# DS145-1_0-B.net
KiCad netlist of a schematic drawn in Altium Designer
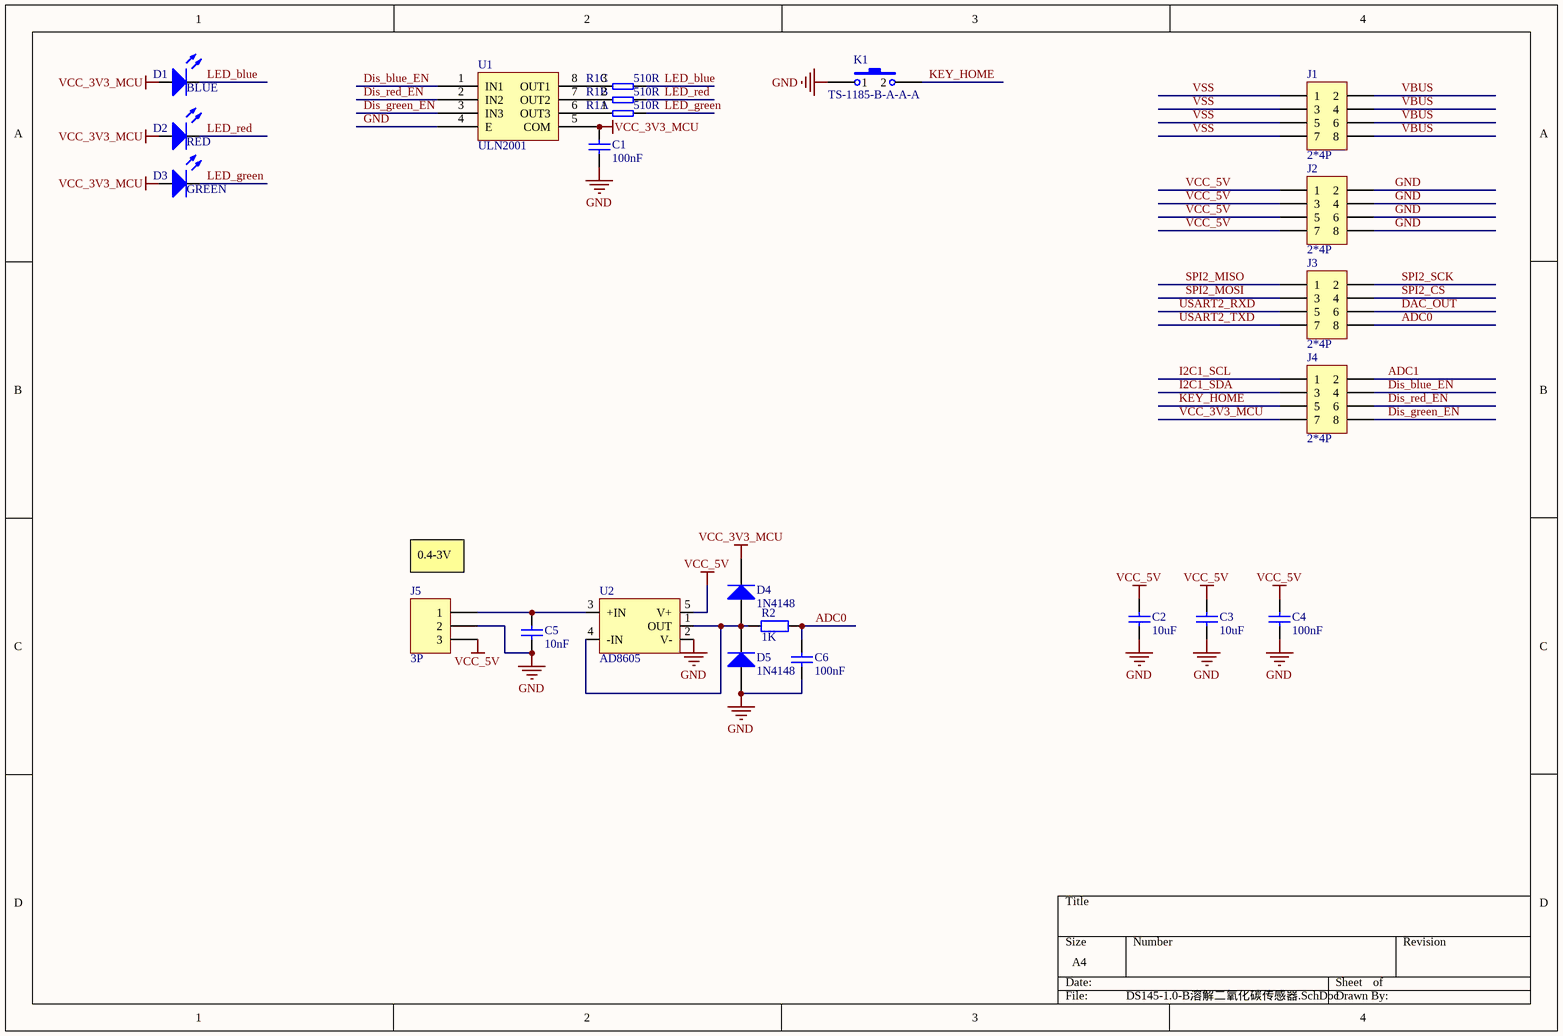
[diagram p0: DS145-1.0-B溶解二氧化碳传感器.SchDoc]

(export (version "E")
  (design (tool "Eeschema 10.0.6"))
  (components
    (comp (ref "C1")
      (value "100nF")
      (footprint "0603CAP")
      (description "贴片电容")
      (fields (field (name "Comment") "SMDCAP00013"))
      (libsource (lib "AD_SCH") (part "MLCC 100nF 50V ±10％ 0603"))
    )
    (comp (ref "C2")
      (value "10uF")
      (footprint "0603CAP")
      (description "贴片电容")
      (fields (field (name "Comment") "SMDCAP00016"))
      (libsource (lib "AD_SCH") (part "MLCC 10uF 50V ±10％ 0603"))
    )
    (comp (ref "C3")
      (value "10uF")
      (footprint "0603CAP")
      (description "贴片电容")
      (fields (field (name "Comment") "SMDCAP00016"))
      (libsource (lib "AD_SCH") (part "MLCC 10uF 50V ±10％ 0603"))
    )
    (comp (ref "C4")
      (value "100nF")
      (footprint "0603CAP")
      (description "贴片电容")
      (fields (field (name "Comment") "SMDCAP00013"))
      (libsource (lib "AD_SCH") (part "MLCC 100nF 50V ±10％ 0603"))
    )
    (comp (ref "C5")
      (value "10nF")
      (footprint "0603CAP")
      (description "贴片电容")
      (fields (field (name "Comment") "SMDCAP00013"))
      (libsource (lib "AD_SCH") (part "MLCC 100nF 50V ±10％ 0603"))
    )
    (comp (ref "C6")
      (value "100nF")
      (footprint "0603CAP")
      (description "贴片电容")
      (fields (field (name "Comment") "SMDCAP00013"))
      (libsource (lib "AD_SCH") (part "MLCC 100nF 50V ±10％ 0603"))
    )
    (comp (ref "D1")
      (value "BLUE")
      (footprint "LED_0805")
      (description "贴片LED")
      (fields (field (name "Comment") "SMDLED00010"))
      (libsource (lib "AD_SCH") (part "Chip 蓝色LED 0805"))
    )
    (comp (ref "D2")
      (value "RED")
      (footprint "LED_0805")
      (description "贴片LED")
      (fields (field (name "Comment") "SMDLED00003"))
      (libsource (lib "AD_SCH") (part "Chip 红色LED 0805"))
    )
    (comp (ref "D3")
      (value "GREEN")
      (footprint "LED_0805")
      (description "贴片LED")
      (fields (field (name "Comment") "Chip 翠绿LED 0805"))
      (libsource (lib "AD_SCH") (part "Chip 翠绿LED 0805"))
    )
    (comp (ref "D4")
      (value "1N4148")
      (footprint "SOD-123")
      (description "贴片开关二极管 T4")
      (fields (field (name "Comment") "DIPDIODE02001"))
      (libsource (lib "AD_SCH") (part "1N4148W"))
    )
    (comp (ref "D5")
      (value "1N4148")
      (footprint "SOD-123")
      (description "贴片开关二极管 T4")
      (fields (field (name "Comment") "DIPDIODE02001"))
      (libsource (lib "AD_SCH") (part "1N4148W"))
    )
    (comp (ref "J1")
      (value "2*4P")
      (footprint "X1321WVS-2x04J-C40D53")
      (description "双排针2x4P 立贴 1.27mm")
      (fields (field (name "Comment") "X1321WVS-2x04J-C40D53"))
      (libsource (lib "AD_SCH") (part "X1321WVS-2x04J-C40D53"))
    )
    (comp (ref "J2")
      (value "2*4P")
      (footprint "X1321WVS-2x04J-C40D53")
      (description "双排针2x4P 立贴 1.27mm")
      (fields (field (name "Comment") "X1321WVS-2x04J-C40D53"))
      (libsource (lib "AD_SCH") (part "X1321WVS-2x04J-C40D53"))
    )
    (comp (ref "J3")
      (value "2*4P")
      (footprint "X1321WVS-2x04J-C40D53")
      (description "双排针2x4P 立贴 1.27mm")
      (fields (field (name "Comment") "X1321WVS-2x04J-C40D53"))
      (libsource (lib "AD_SCH") (part "X1321WVS-2x04J-C40D53"))
    )
    (comp (ref "J4")
      (value "2*4P")
      (footprint "X1321WVS-2x04J-C40D53")
      (description "双排针2x4P 立贴 1.27mm")
      (fields (field (name "Comment") "X1321WVS-2x04J-C40D53"))
      (libsource (lib "AD_SCH") (part "X1321WVS-2x04J-C40D53"))
    )
    (comp (ref "J5")
      (value "3P")
      (footprint "SIP3")
      (description "单排直针")
      (fields (field (name "Comment") "SL000000042"))
      (libsource (lib "AD_SCH") (part "DIP3 单排直针 间距2.54mm 针长11mm 铜"))
    )
    (comp (ref "K1")
      (value "TS-1185-B-A-A-A")
      (footprint "KEY_TS-1185-x-A-A-A")
      (description "轻触开关")
      (libsource (lib "AD_SCH") (part "TS-1185-B-A-A-A"))
    )
    (comp (ref "R1")
      (value "510R")
      (footprint "0603RES_Pack4")
      (description "贴片排阻")
      (fields (field (name "Comment") "SMDRES05003"))
      (libsource (lib "AD_SCH") (part "Chip R*4 510R 1/16W ±5％ 0603"))
    )
    (comp (ref "R2")
      (value "1K")
      (footprint "0603RES")
      (description "贴片电阻")
      (fields (field (name "Comment") "SMDRES00034"))
      (libsource (lib "AD_SCH") (part "Chip 1K 1/16W ±1％ 0603"))
    )
    (comp (ref "U1")
      (value "ULN2001")
      (footprint "SO-8")
      (description "电机驱动芯片")
      (fields (field (name "Comment") "SMDIC000018"))
      (libsource (lib "AD_SCH") (part "ULN2001 SOP-8"))
    )
    (comp (ref "U2")
      (value "AD8605")
      (footprint "SOT23-5")
      (description "运放芯片")
      (libsource (lib "AD_SCH") (part "AD8605 SOT23-5"))
    )
  )
  (nets
    (net (code "1") (name "/ADC0") (class "Default")
      (node (ref "C6") (pin "2") (pinfunction "2_2") (pintype "passive"))
      (node (ref "J3") (pin "8") (pinfunction "8_8") (pintype "passive"))
      (node (ref "R2") (pin "2") (pinfunction "2_2") (pintype "passive"))
    )
    (net (code "2") (name "/ADC1") (class "Default")
      (node (ref "J4") (pin "2") (pinfunction "2_2") (pintype "passive"))
    )
    (net (code "3") (name "/DAC_OUT") (class "Default")
      (node (ref "J3") (pin "6") (pinfunction "6_6") (pintype "passive"))
    )
    (net (code "4") (name "/Dis_blue_EN") (class "Default")
      (node (ref "J4") (pin "4") (pinfunction "4_4") (pintype "passive"))
      (node (ref "U1") (pin "1") (pinfunction "IN1_1") (pintype "passive"))
    )
    (net (code "5") (name "/Dis_green_EN") (class "Default")
      (node (ref "J4") (pin "8") (pinfunction "8_8") (pintype "passive"))
      (node (ref "U1") (pin "3") (pinfunction "IN3_3") (pintype "passive"))
    )
    (net (code "6") (name "/Dis_red_EN") (class "Default")
      (node (ref "J4") (pin "6") (pinfunction "6_6") (pintype "passive"))
      (node (ref "U1") (pin "2") (pinfunction "IN2_2") (pintype "passive"))
    )
    (net (code "7") (name "/I2C1_SCL") (class "Default")
      (node (ref "J4") (pin "1") (pinfunction "1_1") (pintype "passive"))
    )
    (net (code "8") (name "/I2C1_SDA") (class "Default")
      (node (ref "J4") (pin "3") (pinfunction "3_3") (pintype "passive"))
    )
    (net (code "9") (name "/KEY_HOME") (class "Default")
      (node (ref "J4") (pin "5") (pinfunction "5_5") (pintype "passive"))
      (node (ref "K1") (pin "2") (pinfunction "2_2") (pintype "passive"))
    )
    (net (code "10") (name "/LED_blue") (class "Default")
      (node (ref "D1") (pin "2") (pinfunction "K_2") (pintype "passive"))
      (node (ref "R1") (pin "6") (pinfunction "6_6") (pintype "passive"))
    )
    (net (code "11") (name "/LED_green") (class "Default")
      (node (ref "D3") (pin "2") (pinfunction "K_2") (pintype "passive"))
      (node (ref "R1") (pin "8") (pinfunction "8_8") (pintype "passive"))
    )
    (net (code "12") (name "/LED_red") (class "Default")
      (node (ref "D2") (pin "2") (pinfunction "K_2") (pintype "passive"))
      (node (ref "R1") (pin "7") (pinfunction "7_7") (pintype "passive"))
    )
    (net (code "13") (name "/SPI2_CS") (class "Default")
      (node (ref "J3") (pin "4") (pinfunction "4_4") (pintype "passive"))
    )
    (net (code "14") (name "/SPI2_MISO") (class "Default")
      (node (ref "J3") (pin "1") (pinfunction "1_1") (pintype "passive"))
    )
    (net (code "15") (name "/SPI2_MOSI") (class "Default")
      (node (ref "J3") (pin "3") (pinfunction "3_3") (pintype "passive"))
    )
    (net (code "16") (name "/SPI2_SCK") (class "Default")
      (node (ref "J3") (pin "2") (pinfunction "2_2") (pintype "passive"))
    )
    (net (code "17") (name "/USART2_RXD") (class "Default")
      (node (ref "J3") (pin "5") (pinfunction "5_5") (pintype "passive"))
    )
    (net (code "18") (name "/USART2_TXD") (class "Default")
      (node (ref "J3") (pin "7") (pinfunction "7_7") (pintype "passive"))
    )
    (net (code "19") (name "/VBUS") (class "Default")
      (node (ref "J1") (pin "2") (pinfunction "2_2") (pintype "passive"))
      (node (ref "J1") (pin "4") (pinfunction "4_4") (pintype "passive"))
      (node (ref "J1") (pin "6") (pinfunction "6_6") (pintype "passive"))
      (node (ref "J1") (pin "8") (pinfunction "8_8") (pintype "passive"))
    )
    (net (code "20") (name "/VSS") (class "Default")
      (node (ref "J1") (pin "1") (pinfunction "1_1") (pintype "passive"))
      (node (ref "J1") (pin "3") (pinfunction "3_3") (pintype "passive"))
      (node (ref "J1") (pin "5") (pinfunction "5_5") (pintype "passive"))
      (node (ref "J1") (pin "7") (pinfunction "7_7") (pintype "passive"))
    )
    (net (code "21") (name "GND") (class "Default")
      (node (ref "C1") (pin "1") (pinfunction "1_1") (pintype "passive"))
      (node (ref "C2") (pin "1") (pinfunction "1_1") (pintype "passive"))
      (node (ref "C3") (pin "1") (pinfunction "1_1") (pintype "passive"))
      (node (ref "C4") (pin "1") (pinfunction "1_1") (pintype "passive"))
      (node (ref "C5") (pin "1") (pinfunction "1_1") (pintype "passive"))
      (node (ref "C6") (pin "1") (pinfunction "1_1") (pintype "passive"))
      (node (ref "D5") (pin "1") (pinfunction "A_1") (pintype "passive"))
      (node (ref "J2") (pin "2") (pinfunction "2_2") (pintype "passive"))
      (node (ref "J2") (pin "4") (pinfunction "4_4") (pintype "passive"))
      (node (ref "J2") (pin "6") (pinfunction "6_6") (pintype "passive"))
      (node (ref "J2") (pin "8") (pinfunction "8_8") (pintype "passive"))
      (node (ref "J5") (pin "2") (pinfunction "2_2") (pintype "passive"))
      (node (ref "K1") (pin "1") (pinfunction "1_1") (pintype "passive"))
      (node (ref "U1") (pin "4") (pinfunction "E_4") (pintype "passive"))
      (node (ref "U2") (pin "2") (pinfunction "V-_2") (pintype "passive"))
    )
    (net (code "22") (name "Net-(D4-A)") (class "Default")
      (node (ref "D4") (pin "1") (pinfunction "A_1") (pintype "passive"))
      (node (ref "D5") (pin "2") (pinfunction "K_2") (pintype "passive"))
      (node (ref "R2") (pin "1") (pinfunction "1_1") (pintype "passive"))
      (node (ref "U2") (pin "1") (pinfunction "OUT_1") (pintype "passive"))
      (node (ref "U2") (pin "4") (pinfunction "-IN_4") (pintype "passive"))
    )
    (net (code "23") (name "Net-(U1-OUT1)") (class "Default")
      (node (ref "R1") (pin "3") (pinfunction "3_3") (pintype "passive"))
      (node (ref "U1") (pin "8") (pinfunction "OUT1_8") (pintype "passive"))
    )
    (net (code "24") (name "Net-(U1-OUT2)") (class "Default")
      (node (ref "R1") (pin "2") (pinfunction "2_2") (pintype "passive"))
      (node (ref "U1") (pin "7") (pinfunction "OUT2_7") (pintype "passive"))
    )
    (net (code "25") (name "Net-(U1-OUT3)") (class "Default")
      (node (ref "R1") (pin "1") (pinfunction "1_1") (pintype "passive"))
      (node (ref "U1") (pin "6") (pinfunction "OUT3_6") (pintype "passive"))
    )
    (net (code "26") (name "Net-(U2-+IN)") (class "Default")
      (node (ref "C5") (pin "2") (pinfunction "2_2") (pintype "passive"))
      (node (ref "J5") (pin "1") (pinfunction "1_1") (pintype "passive"))
      (node (ref "U2") (pin "3") (pinfunction "+IN_3") (pintype "passive"))
    )
    (net (code "27") (name "VCC_3V3_MCU") (class "Default")
      (node (ref "C1") (pin "2") (pinfunction "2_2") (pintype "passive"))
      (node (ref "D1") (pin "1") (pinfunction "A_1") (pintype "passive"))
      (node (ref "D2") (pin "1") (pinfunction "A_1") (pintype "passive"))
      (node (ref "D3") (pin "1") (pinfunction "A_1") (pintype "passive"))
      (node (ref "D4") (pin "2") (pinfunction "K_2") (pintype "passive"))
      (node (ref "J4") (pin "7") (pinfunction "7_7") (pintype "passive"))
      (node (ref "U1") (pin "5") (pinfunction "COM_5") (pintype "passive"))
    )
    (net (code "28") (name "VCC_5V") (class "Default")
      (node (ref "C2") (pin "2") (pinfunction "2_2") (pintype "passive"))
      (node (ref "C3") (pin "2") (pinfunction "2_2") (pintype "passive"))
      (node (ref "C4") (pin "2") (pinfunction "2_2") (pintype "passive"))
      (node (ref "J2") (pin "1") (pinfunction "1_1") (pintype "passive"))
      (node (ref "J2") (pin "3") (pinfunction "3_3") (pintype "passive"))
      (node (ref "J2") (pin "5") (pinfunction "5_5") (pintype "passive"))
      (node (ref "J2") (pin "7") (pinfunction "7_7") (pintype "passive"))
      (node (ref "J5") (pin "3") (pinfunction "3_3") (pintype "passive"))
      (node (ref "U2") (pin "5") (pinfunction "V+_5") (pintype "passive"))
    )
  )
)
